# uzed-hmdi-test.net
KiCad netlist of a schematic drawn in EAGLE
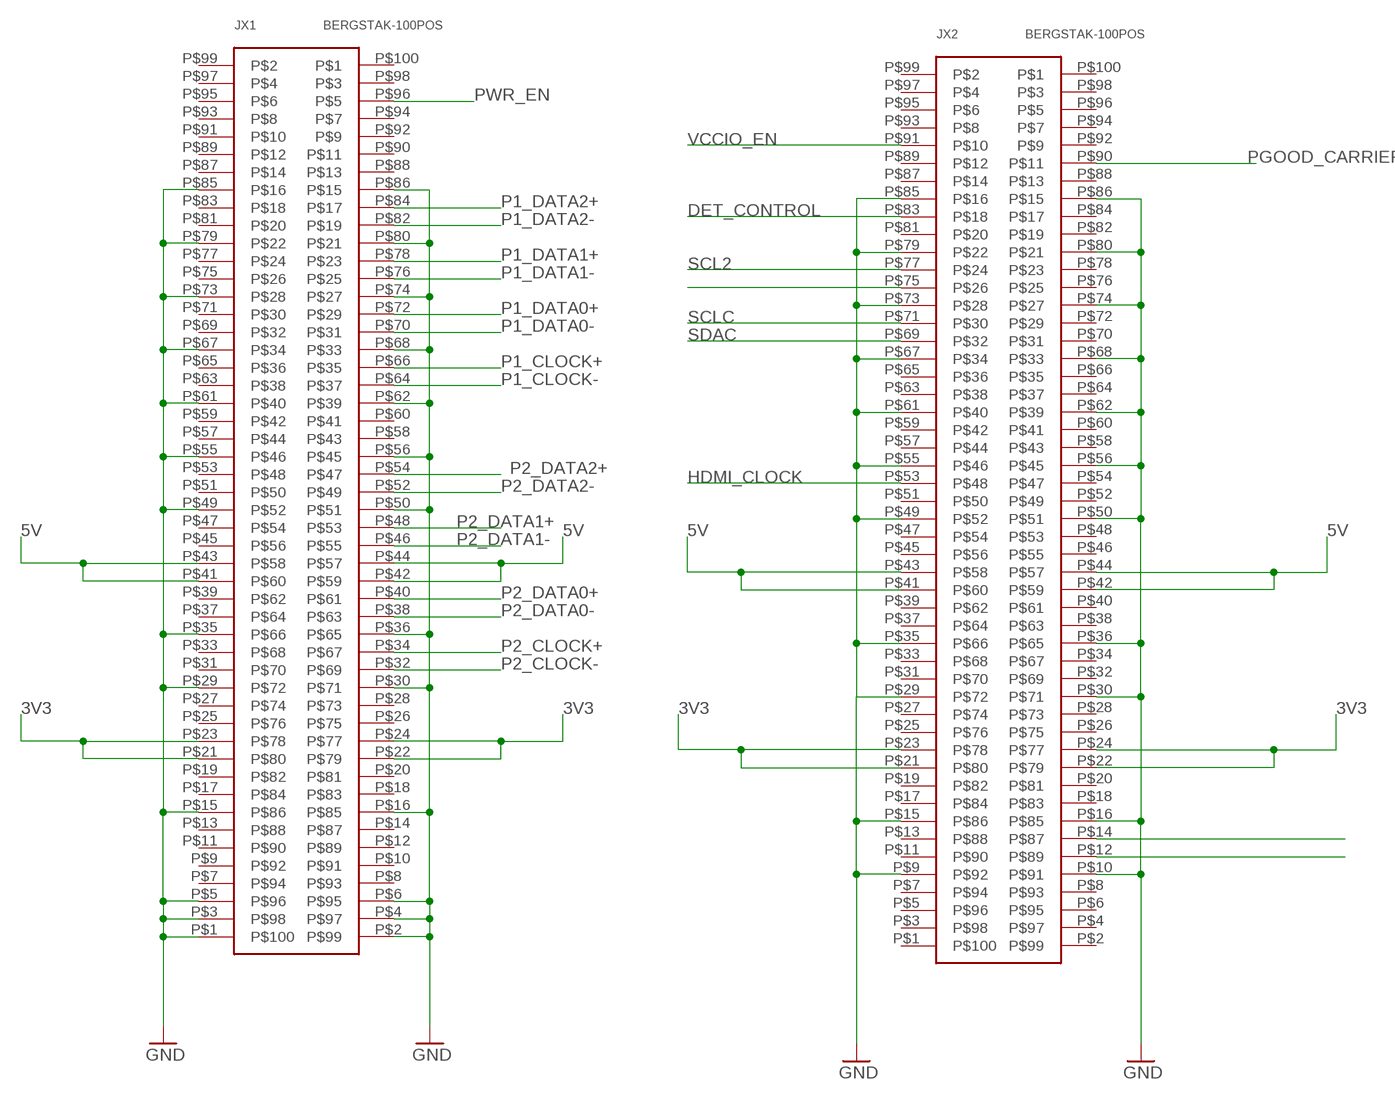
[diagram p0: schematic, sheet 1]
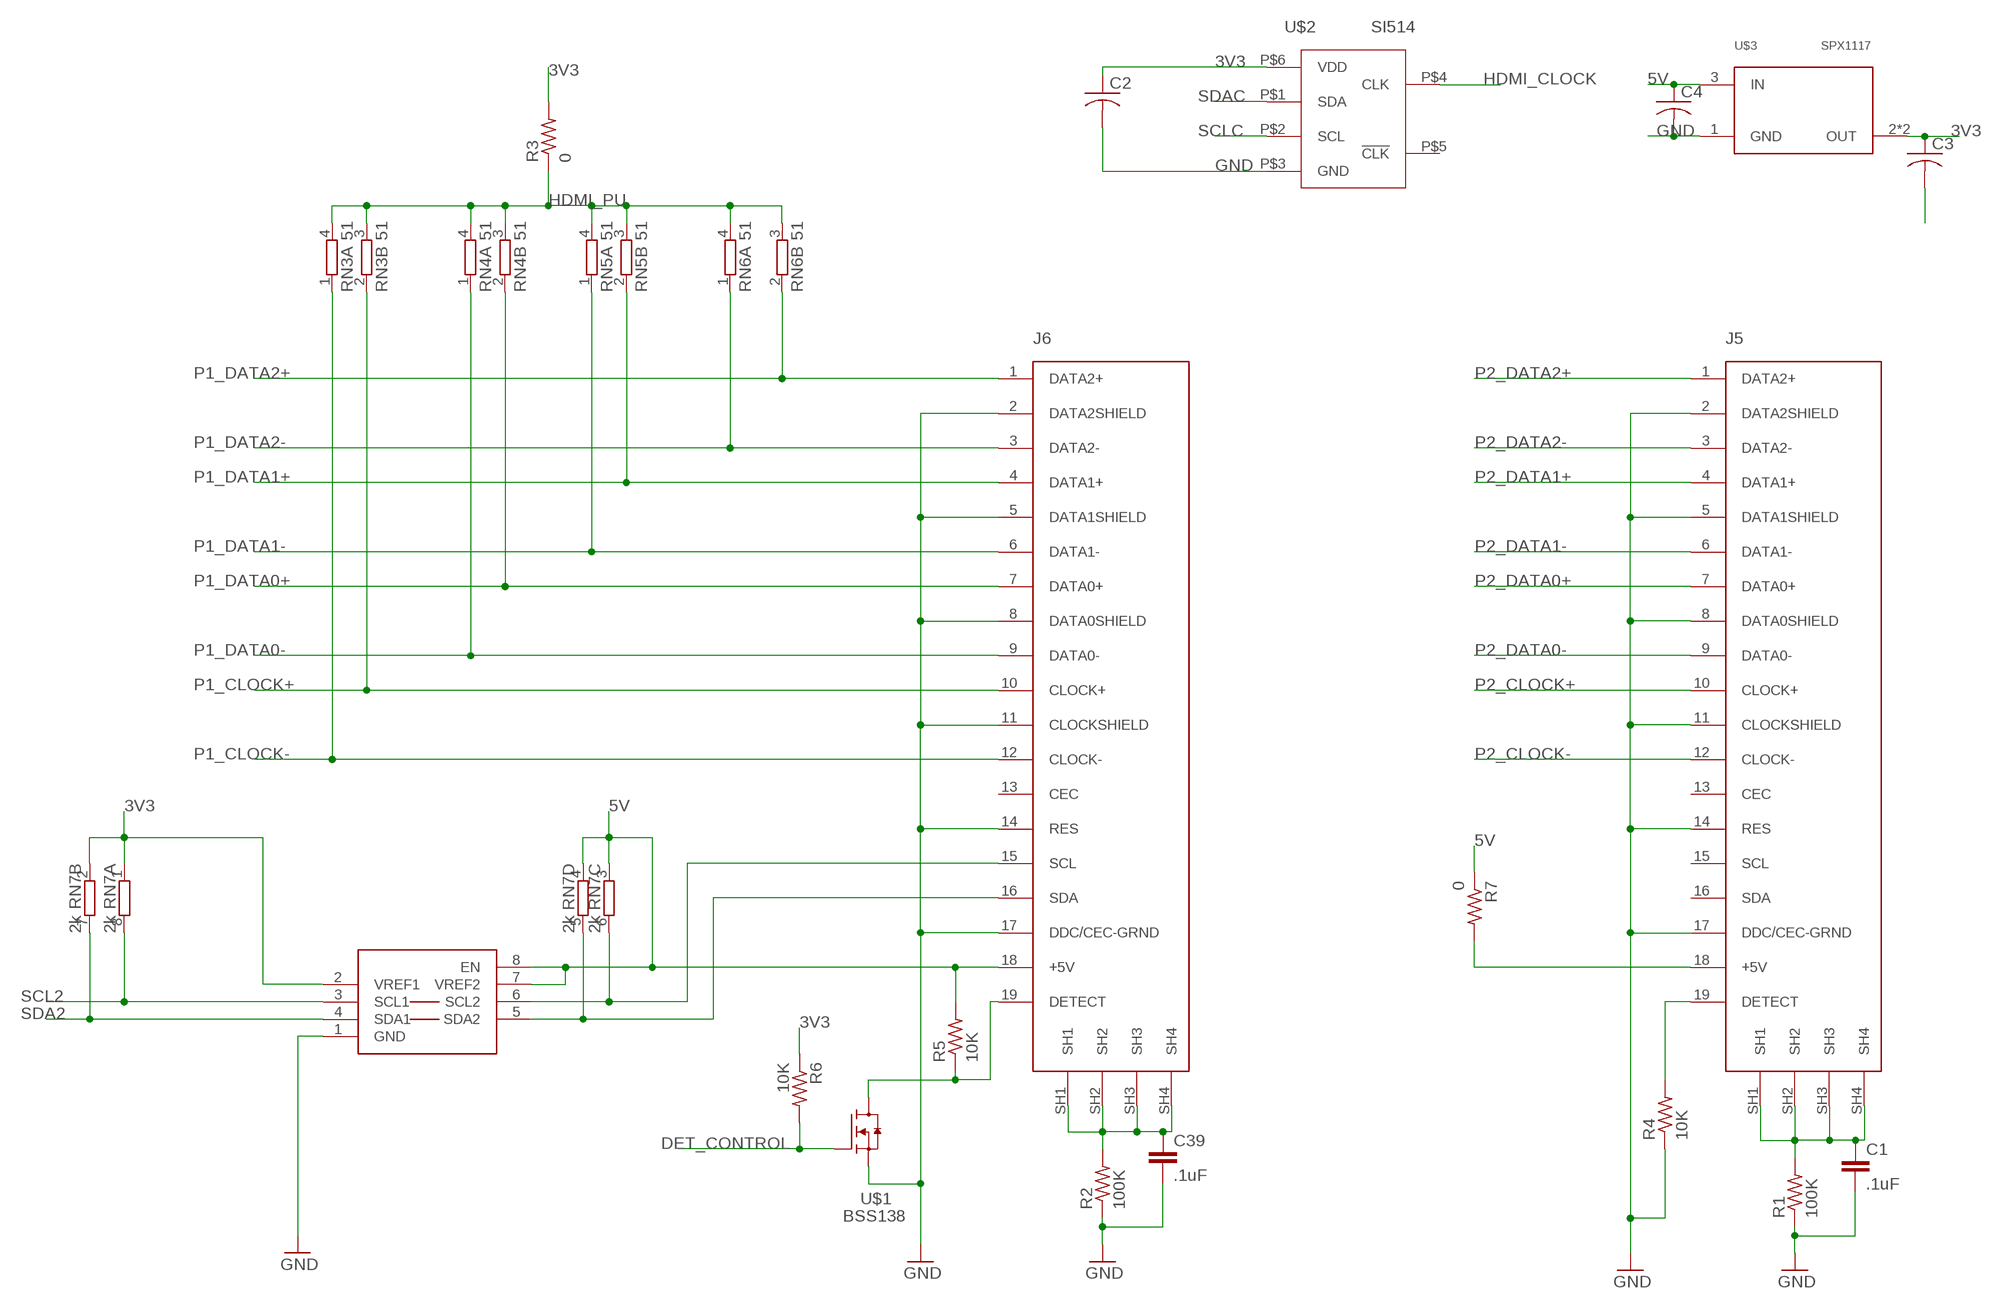
[diagram p1: schematic, sheet 2]

(export (version "E")
  (design (tool "Eeschema 10.0.6"))
  (components
    (comp (ref "JX1")
      (value "BERGSTAK-100POS")
      (footprint "eagle-import:BERG100POS")
      (libsource (lib "eagle-import") (part "BERGSTAK-100POS"))
    )
    (comp (ref "JX2")
      (value "BERGSTAK-100POS")
      (footprint "eagle-import:BERG100POS")
      (libsource (lib "eagle-import") (part "BERGSTAK-100POS"))
    )
    (comp (ref "C1")
      (value ".1uF")
      (footprint "eagle-import:C0603K")
      (libsource (lib "eagle-import") (part "C-EUC0603K"))
    )
    (comp (ref "C2")
      (value "C-USC0603")
      (footprint "eagle-import:C0603")
      (libsource (lib "eagle-import") (part "C-USC0603"))
    )
    (comp (ref "C3")
      (value "C-USC0603")
      (footprint "eagle-import:C0603")
      (libsource (lib "eagle-import") (part "C-USC0603"))
    )
    (comp (ref "C4")
      (value "C-USC0603")
      (footprint "eagle-import:C0603")
      (libsource (lib "eagle-import") (part "C-USC0603"))
    )
    (comp (ref "C39")
      (value ".1uF")
      (footprint "eagle-import:C0603K")
      (libsource (lib "eagle-import") (part "C-EUC0603K"))
    )
    (comp (ref "J5")
      (value "HDMI-TYPE-A-RECEPTICALFCI10029449")
      (footprint "eagle-import:FCI-HDMI-TYPE-A-RECEPT")
      (libsource (lib "eagle-import") (part "HDMI-TYPE-A-RECEPTICALFCI10029449"))
    )
    (comp (ref "J6")
      (value "HDMI-TYPE-A-RECEPTICALFCI10029449")
      (footprint "eagle-import:FCI-HDMI-TYPE-A-RECEPT")
      (libsource (lib "eagle-import") (part "HDMI-TYPE-A-RECEPTICALFCI10029449"))
    )
    (comp (ref "PCA9306")
      (value "PCA9306")
      (footprint "eagle-import:PSOP-8")
      (libsource (lib "eagle-import") (part "PCA9306"))
    )
    (comp (ref "R1")
      (value "100K")
      (footprint "eagle-import:R0603")
      (libsource (lib "eagle-import") (part "R-US_R0603"))
    )
    (comp (ref "R2")
      (value "100K")
      (footprint "eagle-import:R0603")
      (libsource (lib "eagle-import") (part "R-US_R0603"))
    )
    (comp (ref "R3")
      (value "0")
      (footprint "eagle-import:R0603")
      (libsource (lib "eagle-import") (part "rcl_334_R-US_R0603"))
    )
    (comp (ref "R4")
      (value "10K")
      (footprint "eagle-import:R0603")
      (libsource (lib "eagle-import") (part "R-US_R0603"))
    )
    (comp (ref "R5")
      (value "10K")
      (footprint "eagle-import:R0603")
      (libsource (lib "eagle-import") (part "R-US_R0603"))
    )
    (comp (ref "R6")
      (value "10K")
      (footprint "eagle-import:R0603")
      (libsource (lib "eagle-import") (part "R-US_R0603"))
    )
    (comp (ref "R7")
      (value "0")
      (footprint "eagle-import:R0603")
      (libsource (lib "eagle-import") (part "R-US_R0603"))
    )
    (comp (ref "RN3")
      (value "51")
      (footprint "eagle-import:EXB34V")
      (libsource (lib "eagle-import") (part "2R-NEXB34V"))
    )
    (comp (ref "RN4")
      (value "51")
      (footprint "eagle-import:EXB34V")
      (libsource (lib "eagle-import") (part "2R-NEXB34V"))
    )
    (comp (ref "RN5")
      (value "51")
      (footprint "eagle-import:EXB34V")
      (libsource (lib "eagle-import") (part "2R-NEXB34V"))
    )
    (comp (ref "RN6")
      (value "51")
      (footprint "eagle-import:EXB34V")
      (libsource (lib "eagle-import") (part "2R-NEXB34V"))
    )
    (comp (ref "RN7")
      (value "2k")
      (footprint "eagle-import:0603-ARV")
      (libsource (lib "eagle-import") (part "4R-N0603-ARV"))
    )
    (comp (ref "U$1")
      (value "BSS138")
      (footprint "eagle-import:SOT23")
      (libsource (lib "eagle-import") (part "BSS138"))
    )
    (comp (ref "U$2")
      (value "SI514")
      (footprint "eagle-import:XTAL-6PIN")
      (libsource (lib "eagle-import") (part "SI514"))
    )
    (comp (ref "U$3")
      (value "SPX1117")
      (footprint "eagle-import:SOT223")
      (libsource (lib "eagle-import") (part "SPX1117"))
    )
  )
  (nets
    (net (code "1") (name "3V3") (class "Default")
      (node (ref "C2") (pin "1") (pinfunction "1_1") (pintype "passive"))
      (node (ref "C3") (pin "1") (pinfunction "1_1") (pintype "passive"))
      (node (ref "JX1") (pin "P$21") (pinfunction "P$80_P$21") (pintype "bidirectional"))
      (node (ref "JX1") (pin "P$22") (pinfunction "P$79_P$22") (pintype "bidirectional"))
      (node (ref "JX1") (pin "P$23") (pinfunction "P$78_P$23") (pintype "bidirectional"))
      (node (ref "JX1") (pin "P$24") (pinfunction "P$77_P$24") (pintype "bidirectional"))
      (node (ref "JX2") (pin "P$21") (pinfunction "P$80_P$21") (pintype "bidirectional"))
      (node (ref "JX2") (pin "P$22") (pinfunction "P$79_P$22") (pintype "bidirectional"))
      (node (ref "JX2") (pin "P$23") (pinfunction "P$78_P$23") (pintype "bidirectional"))
      (node (ref "JX2") (pin "P$24") (pinfunction "P$77_P$24") (pintype "bidirectional"))
      (node (ref "PCA9306") (pin "2") (pinfunction "VREF1_2") (pintype "bidirectional"))
      (node (ref "R3") (pin "2") (pinfunction "2_2") (pintype "passive"))
      (node (ref "R6") (pin "1") (pinfunction "1_1") (pintype "passive"))
      (node (ref "RN7") (pin "1") (pinfunction "1_1") (pintype "passive"))
      (node (ref "RN7") (pin "2") (pinfunction "1_2") (pintype "passive"))
      (node (ref "U$2") (pin "P$6") (pinfunction "VDD_P$6") (pintype "bidirectional"))
      (node (ref "U$3") (pin "2") (pinfunction "OUT_2") (pintype "bidirectional"))
      (node (ref "U$3") (pin "4") (pinfunction "OUT_4") (pintype "bidirectional"))
    )
    (net (code "2") (name "5V") (class "Default")
      (node (ref "C4") (pin "1") (pinfunction "1_1") (pintype "passive"))
      (node (ref "J6") (pin "18") (pinfunction "+5V_18") (pintype "bidirectional"))
      (node (ref "JX1") (pin "P$41") (pinfunction "P$60_P$41") (pintype "bidirectional"))
      (node (ref "JX1") (pin "P$42") (pinfunction "P$59_P$42") (pintype "bidirectional"))
      (node (ref "JX1") (pin "P$43") (pinfunction "P$58_P$43") (pintype "bidirectional"))
      (node (ref "JX1") (pin "P$44") (pinfunction "P$57_P$44") (pintype "bidirectional"))
      (node (ref "JX2") (pin "P$41") (pinfunction "P$60_P$41") (pintype "bidirectional"))
      (node (ref "JX2") (pin "P$42") (pinfunction "P$59_P$42") (pintype "bidirectional"))
      (node (ref "JX2") (pin "P$43") (pinfunction "P$58_P$43") (pintype "bidirectional"))
      (node (ref "JX2") (pin "P$44") (pinfunction "P$57_P$44") (pintype "bidirectional"))
      (node (ref "PCA9306") (pin "7") (pinfunction "VREF2_7") (pintype "bidirectional"))
      (node (ref "PCA9306") (pin "8") (pinfunction "EN_8") (pintype "bidirectional"))
      (node (ref "R5") (pin "2") (pinfunction "2_2") (pintype "passive"))
      (node (ref "R7") (pin "1") (pinfunction "1_1") (pintype "passive"))
      (node (ref "RN7") (pin "3") (pinfunction "1_3") (pintype "passive"))
      (node (ref "RN7") (pin "4") (pinfunction "1_4") (pintype "passive"))
      (node (ref "U$3") (pin "3") (pinfunction "IN_3") (pintype "bidirectional"))
    )
    (net (code "3") (name "DET_CONTROL") (class "Default")
      (node (ref "JX2") (pin "P$83") (pinfunction "P$18_P$83") (pintype "bidirectional"))
      (node (ref "R6") (pin "2") (pinfunction "2_2") (pintype "passive"))
      (node (ref "U$1") (pin "1") (pinfunction "G_1") (pintype "passive"))
    )
    (net (code "4") (name "GND") (class "Default")
      (node (ref "C1") (pin "2") (pinfunction "2_2") (pintype "passive"))
      (node (ref "C2") (pin "2") (pinfunction "2_2") (pintype "passive"))
      (node (ref "C3") (pin "2") (pinfunction "2_2") (pintype "passive"))
      (node (ref "C39") (pin "2") (pinfunction "2_2") (pintype "passive"))
      (node (ref "C4") (pin "2") (pinfunction "2_2") (pintype "passive"))
      (node (ref "J5") (pin "11") (pinfunction "CLOCKSHIELD_11") (pintype "bidirectional"))
      (node (ref "J5") (pin "14") (pinfunction "RES_14") (pintype "bidirectional"))
      (node (ref "J5") (pin "17") (pinfunction "DDC/CEC-GRND_17") (pintype "bidirectional"))
      (node (ref "J5") (pin "2") (pinfunction "DATA2SHIELD_2") (pintype "bidirectional"))
      (node (ref "J5") (pin "5") (pinfunction "DATA1SHIELD_5") (pintype "bidirectional"))
      (node (ref "J5") (pin "8") (pinfunction "DATA0SHIELD_8") (pintype "bidirectional"))
      (node (ref "J6") (pin "11") (pinfunction "CLOCKSHIELD_11") (pintype "bidirectional"))
      (node (ref "J6") (pin "14") (pinfunction "RES_14") (pintype "bidirectional"))
      (node (ref "J6") (pin "17") (pinfunction "DDC/CEC-GRND_17") (pintype "bidirectional"))
      (node (ref "J6") (pin "2") (pinfunction "DATA2SHIELD_2") (pintype "bidirectional"))
      (node (ref "J6") (pin "5") (pinfunction "DATA1SHIELD_5") (pintype "bidirectional"))
      (node (ref "J6") (pin "8") (pinfunction "DATA0SHIELD_8") (pintype "bidirectional"))
      (node (ref "JX1") (pin "P$1") (pinfunction "P$100_P$1") (pintype "bidirectional"))
      (node (ref "JX1") (pin "P$15") (pinfunction "P$86_P$15") (pintype "bidirectional"))
      (node (ref "JX1") (pin "P$16") (pinfunction "P$85_P$16") (pintype "bidirectional"))
      (node (ref "JX1") (pin "P$2") (pinfunction "P$99_P$2") (pintype "bidirectional"))
      (node (ref "JX1") (pin "P$29") (pinfunction "P$72_P$29") (pintype "bidirectional"))
      (node (ref "JX1") (pin "P$3") (pinfunction "P$98_P$3") (pintype "bidirectional"))
      (node (ref "JX1") (pin "P$30") (pinfunction "P$71_P$30") (pintype "bidirectional"))
      (node (ref "JX1") (pin "P$35") (pinfunction "P$66_P$35") (pintype "bidirectional"))
      (node (ref "JX1") (pin "P$36") (pinfunction "P$65_P$36") (pintype "bidirectional"))
      (node (ref "JX1") (pin "P$4") (pinfunction "P$97_P$4") (pintype "bidirectional"))
      (node (ref "JX1") (pin "P$49") (pinfunction "P$52_P$49") (pintype "bidirectional"))
      (node (ref "JX1") (pin "P$5") (pinfunction "P$96_P$5") (pintype "bidirectional"))
      (node (ref "JX1") (pin "P$50") (pinfunction "P$51_P$50") (pintype "bidirectional"))
      (node (ref "JX1") (pin "P$55") (pinfunction "P$46_P$55") (pintype "bidirectional"))
      (node (ref "JX1") (pin "P$56") (pinfunction "P$45_P$56") (pintype "bidirectional"))
      (node (ref "JX1") (pin "P$6") (pinfunction "P$95_P$6") (pintype "bidirectional"))
      (node (ref "JX1") (pin "P$61") (pinfunction "P$40_P$61") (pintype "bidirectional"))
      (node (ref "JX1") (pin "P$62") (pinfunction "P$39_P$62") (pintype "bidirectional"))
      (node (ref "JX1") (pin "P$67") (pinfunction "P$34_P$67") (pintype "bidirectional"))
      (node (ref "JX1") (pin "P$68") (pinfunction "P$33_P$68") (pintype "bidirectional"))
      (node (ref "JX1") (pin "P$73") (pinfunction "P$28_P$73") (pintype "bidirectional"))
      (node (ref "JX1") (pin "P$74") (pinfunction "P$27_P$74") (pintype "bidirectional"))
      (node (ref "JX1") (pin "P$79") (pinfunction "P$22_P$79") (pintype "bidirectional"))
      (node (ref "JX1") (pin "P$80") (pinfunction "P$21_P$80") (pintype "bidirectional"))
      (node (ref "JX1") (pin "P$85") (pinfunction "P$16_P$85") (pintype "bidirectional"))
      (node (ref "JX1") (pin "P$86") (pinfunction "P$15_P$86") (pintype "bidirectional"))
      (node (ref "JX2") (pin "P$10") (pinfunction "P$91_P$10") (pintype "bidirectional"))
      (node (ref "JX2") (pin "P$15") (pinfunction "P$86_P$15") (pintype "bidirectional"))
      (node (ref "JX2") (pin "P$16") (pinfunction "P$85_P$16") (pintype "bidirectional"))
      (node (ref "JX2") (pin "P$29") (pinfunction "P$72_P$29") (pintype "bidirectional"))
      (node (ref "JX2") (pin "P$30") (pinfunction "P$71_P$30") (pintype "bidirectional"))
      (node (ref "JX2") (pin "P$35") (pinfunction "P$66_P$35") (pintype "bidirectional"))
      (node (ref "JX2") (pin "P$36") (pinfunction "P$65_P$36") (pintype "bidirectional"))
      (node (ref "JX2") (pin "P$49") (pinfunction "P$52_P$49") (pintype "bidirectional"))
      (node (ref "JX2") (pin "P$50") (pinfunction "P$51_P$50") (pintype "bidirectional"))
      (node (ref "JX2") (pin "P$55") (pinfunction "P$46_P$55") (pintype "bidirectional"))
      (node (ref "JX2") (pin "P$56") (pinfunction "P$45_P$56") (pintype "bidirectional"))
      (node (ref "JX2") (pin "P$61") (pinfunction "P$40_P$61") (pintype "bidirectional"))
      (node (ref "JX2") (pin "P$62") (pinfunction "P$39_P$62") (pintype "bidirectional"))
      (node (ref "JX2") (pin "P$67") (pinfunction "P$34_P$67") (pintype "bidirectional"))
      (node (ref "JX2") (pin "P$68") (pinfunction "P$33_P$68") (pintype "bidirectional"))
      (node (ref "JX2") (pin "P$73") (pinfunction "P$28_P$73") (pintype "bidirectional"))
      (node (ref "JX2") (pin "P$74") (pinfunction "P$27_P$74") (pintype "bidirectional"))
      (node (ref "JX2") (pin "P$79") (pinfunction "P$22_P$79") (pintype "bidirectional"))
      (node (ref "JX2") (pin "P$80") (pinfunction "P$21_P$80") (pintype "bidirectional"))
      (node (ref "JX2") (pin "P$85") (pinfunction "P$16_P$85") (pintype "bidirectional"))
      (node (ref "JX2") (pin "P$86") (pinfunction "P$15_P$86") (pintype "bidirectional"))
      (node (ref "JX2") (pin "P$9") (pinfunction "P$92_P$9") (pintype "bidirectional"))
      (node (ref "PCA9306") (pin "1") (pinfunction "GND_1") (pintype "bidirectional"))
      (node (ref "R1") (pin "1") (pinfunction "1_1") (pintype "passive"))
      (node (ref "R2") (pin "1") (pinfunction "1_1") (pintype "passive"))
      (node (ref "R4") (pin "1") (pinfunction "1_1") (pintype "passive"))
      (node (ref "U$1") (pin "2") (pinfunction "S_2") (pintype "passive"))
      (node (ref "U$2") (pin "P$3") (pinfunction "GND_P$3") (pintype "bidirectional"))
      (node (ref "U$3") (pin "1") (pinfunction "GND_1") (pintype "bidirectional"))
    )
    (net (code "5") (name "HDMI_CLOCK") (class "Default")
      (node (ref "JX2") (pin "P$53") (pinfunction "P$48_P$53") (pintype "bidirectional"))
      (node (ref "U$2") (pin "P$4") (pinfunction "CLK_P$4") (pintype "bidirectional"))
    )
    (net (code "6") (name "HDMI_PU") (class "Default")
      (node (ref "R3") (pin "1") (pinfunction "1_1") (pintype "passive"))
      (node (ref "RN3") (pin "3") (pinfunction "2_3") (pintype "passive"))
      (node (ref "RN3") (pin "4") (pinfunction "2_4") (pintype "passive"))
      (node (ref "RN4") (pin "3") (pinfunction "2_3") (pintype "passive"))
      (node (ref "RN4") (pin "4") (pinfunction "2_4") (pintype "passive"))
      (node (ref "RN5") (pin "3") (pinfunction "2_3") (pintype "passive"))
      (node (ref "RN5") (pin "4") (pinfunction "2_4") (pintype "passive"))
      (node (ref "RN6") (pin "3") (pinfunction "2_3") (pintype "passive"))
      (node (ref "RN6") (pin "4") (pinfunction "2_4") (pintype "passive"))
    )
    (net (code "7") (name "Net-(C1-Pad1)") (class "Default")
      (node (ref "C1") (pin "1") (pinfunction "1_1") (pintype "passive"))
      (node (ref "J5") (pin "SH1") (pinfunction "SH1_SH1") (pintype "bidirectional"))
      (node (ref "J5") (pin "SH2") (pinfunction "SH2_SH2") (pintype "bidirectional"))
      (node (ref "J5") (pin "SH3") (pinfunction "SH3_SH3") (pintype "bidirectional"))
      (node (ref "J5") (pin "SH4") (pinfunction "SH4_SH4") (pintype "bidirectional"))
      (node (ref "R1") (pin "2") (pinfunction "2_2") (pintype "passive"))
    )
    (net (code "8") (name "Net-(C39-Pad1)") (class "Default")
      (node (ref "C39") (pin "1") (pinfunction "1_1") (pintype "passive"))
      (node (ref "J6") (pin "SH1") (pinfunction "SH1_SH1") (pintype "bidirectional"))
      (node (ref "J6") (pin "SH2") (pinfunction "SH2_SH2") (pintype "bidirectional"))
      (node (ref "J6") (pin "SH3") (pinfunction "SH3_SH3") (pintype "bidirectional"))
      (node (ref "J6") (pin "SH4") (pinfunction "SH4_SH4") (pintype "bidirectional"))
      (node (ref "R2") (pin "2") (pinfunction "2_2") (pintype "passive"))
    )
    (net (code "9") (name "Net-(J5-+5V)") (class "Default")
      (node (ref "J5") (pin "18") (pinfunction "+5V_18") (pintype "bidirectional"))
      (node (ref "R7") (pin "2") (pinfunction "2_2") (pintype "passive"))
    )
    (net (code "10") (name "Net-(J5-DETECT)") (class "Default")
      (node (ref "J5") (pin "19") (pinfunction "DETECT_19") (pintype "bidirectional"))
      (node (ref "R4") (pin "2") (pinfunction "2_2") (pintype "passive"))
    )
    (net (code "11") (name "Net-(J6-DETECT)") (class "Default")
      (node (ref "J6") (pin "19") (pinfunction "DETECT_19") (pintype "bidirectional"))
      (node (ref "R5") (pin "1") (pinfunction "1_1") (pintype "passive"))
      (node (ref "U$1") (pin "3") (pinfunction "D_3") (pintype "passive"))
    )
    (net (code "12") (name "Net-(J6-SCL)") (class "Default")
      (node (ref "J6") (pin "15") (pinfunction "SCL_15") (pintype "bidirectional"))
      (node (ref "PCA9306") (pin "6") (pinfunction "SCL2_6") (pintype "bidirectional"))
      (node (ref "RN7") (pin "6") (pinfunction "2_6") (pintype "passive"))
    )
    (net (code "13") (name "Net-(J6-SDA)") (class "Default")
      (node (ref "J6") (pin "16") (pinfunction "SDA_16") (pintype "bidirectional"))
      (node (ref "PCA9306") (pin "5") (pinfunction "SDA2_5") (pintype "bidirectional"))
      (node (ref "RN7") (pin "5") (pinfunction "2_5") (pintype "passive"))
    )
    (net (code "14") (name "P1_CLOCK+") (class "Default")
      (node (ref "J6") (pin "10") (pinfunction "CLOCK+_10") (pintype "bidirectional"))
      (node (ref "JX1") (pin "P$66") (pinfunction "P$35_P$66") (pintype "bidirectional"))
      (node (ref "RN3") (pin "2") (pinfunction "1_2") (pintype "passive"))
    )
    (net (code "15") (name "P1_CLOCK-") (class "Default")
      (node (ref "J6") (pin "12") (pinfunction "CLOCK-_12") (pintype "bidirectional"))
      (node (ref "JX1") (pin "P$64") (pinfunction "P$37_P$64") (pintype "bidirectional"))
      (node (ref "RN3") (pin "1") (pinfunction "1_1") (pintype "passive"))
    )
    (net (code "16") (name "P1_DATA0+") (class "Default")
      (node (ref "J6") (pin "7") (pinfunction "DATA0+_7") (pintype "bidirectional"))
      (node (ref "JX1") (pin "P$72") (pinfunction "P$29_P$72") (pintype "bidirectional"))
      (node (ref "RN4") (pin "2") (pinfunction "1_2") (pintype "passive"))
    )
    (net (code "17") (name "P1_DATA0-") (class "Default")
      (node (ref "J6") (pin "9") (pinfunction "DATA0-_9") (pintype "bidirectional"))
      (node (ref "JX1") (pin "P$70") (pinfunction "P$31_P$70") (pintype "bidirectional"))
      (node (ref "RN4") (pin "1") (pinfunction "1_1") (pintype "passive"))
    )
    (net (code "18") (name "P1_DATA1+") (class "Default")
      (node (ref "J6") (pin "4") (pinfunction "DATA1+_4") (pintype "bidirectional"))
      (node (ref "JX1") (pin "P$78") (pinfunction "P$23_P$78") (pintype "bidirectional"))
      (node (ref "RN5") (pin "2") (pinfunction "1_2") (pintype "passive"))
    )
    (net (code "19") (name "P1_DATA1-") (class "Default")
      (node (ref "J6") (pin "6") (pinfunction "DATA1-_6") (pintype "bidirectional"))
      (node (ref "JX1") (pin "P$76") (pinfunction "P$25_P$76") (pintype "bidirectional"))
      (node (ref "RN5") (pin "1") (pinfunction "1_1") (pintype "passive"))
    )
    (net (code "20") (name "P1_DATA2+") (class "Default")
      (node (ref "J6") (pin "1") (pinfunction "DATA2+_1") (pintype "bidirectional"))
      (node (ref "JX1") (pin "P$84") (pinfunction "P$17_P$84") (pintype "bidirectional"))
      (node (ref "RN6") (pin "2") (pinfunction "1_2") (pintype "passive"))
    )
    (net (code "21") (name "P1_DATA2-") (class "Default")
      (node (ref "J6") (pin "3") (pinfunction "DATA2-_3") (pintype "bidirectional"))
      (node (ref "JX1") (pin "P$82") (pinfunction "P$19_P$82") (pintype "bidirectional"))
      (node (ref "RN6") (pin "1") (pinfunction "1_1") (pintype "passive"))
    )
    (net (code "22") (name "P2_CLOCK+") (class "Default")
      (node (ref "J5") (pin "10") (pinfunction "CLOCK+_10") (pintype "bidirectional"))
      (node (ref "JX1") (pin "P$34") (pinfunction "P$67_P$34") (pintype "bidirectional"))
    )
    (net (code "23") (name "P2_CLOCK-") (class "Default")
      (node (ref "J5") (pin "12") (pinfunction "CLOCK-_12") (pintype "bidirectional"))
      (node (ref "JX1") (pin "P$32") (pinfunction "P$69_P$32") (pintype "bidirectional"))
    )
    (net (code "24") (name "P2_DATA0+") (class "Default")
      (node (ref "J5") (pin "7") (pinfunction "DATA0+_7") (pintype "bidirectional"))
      (node (ref "JX1") (pin "P$40") (pinfunction "P$61_P$40") (pintype "bidirectional"))
    )
    (net (code "25") (name "P2_DATA0-") (class "Default")
      (node (ref "J5") (pin "9") (pinfunction "DATA0-_9") (pintype "bidirectional"))
      (node (ref "JX1") (pin "P$38") (pinfunction "P$63_P$38") (pintype "bidirectional"))
    )
    (net (code "26") (name "P2_DATA1+") (class "Default")
      (node (ref "J5") (pin "4") (pinfunction "DATA1+_4") (pintype "bidirectional"))
      (node (ref "JX1") (pin "P$48") (pinfunction "P$53_P$48") (pintype "bidirectional"))
    )
    (net (code "27") (name "P2_DATA1-") (class "Default")
      (node (ref "J5") (pin "6") (pinfunction "DATA1-_6") (pintype "bidirectional"))
      (node (ref "JX1") (pin "P$46") (pinfunction "P$55_P$46") (pintype "bidirectional"))
    )
    (net (code "28") (name "P2_DATA2+") (class "Default")
      (node (ref "J5") (pin "1") (pinfunction "DATA2+_1") (pintype "bidirectional"))
      (node (ref "JX1") (pin "P$54") (pinfunction "P$47_P$54") (pintype "bidirectional"))
    )
    (net (code "29") (name "P2_DATA2-") (class "Default")
      (node (ref "J5") (pin "3") (pinfunction "DATA2-_3") (pintype "bidirectional"))
      (node (ref "JX1") (pin "P$52") (pinfunction "P$49_P$52") (pintype "bidirectional"))
    )
    (net (code "30") (name "PGOOD_CARRIER") (class "Default")
      (node (ref "JX2") (pin "P$90") (pinfunction "P$11_P$90") (pintype "bidirectional"))
    )
    (net (code "31") (name "PWR_EN") (class "Default")
      (node (ref "JX1") (pin "P$96") (pinfunction "P$5_P$96") (pintype "bidirectional"))
    )
    (net (code "32") (name "SCL2") (class "Default")
      (node (ref "JX2") (pin "P$77") (pinfunction "P$24_P$77") (pintype "bidirectional"))
      (node (ref "PCA9306") (pin "3") (pinfunction "SCL1_3") (pintype "bidirectional"))
      (node (ref "RN7") (pin "8") (pinfunction "2_8") (pintype "passive"))
    )
    (net (code "33") (name "SCLC") (class "Default")
      (node (ref "JX2") (pin "P$71") (pinfunction "P$30_P$71") (pintype "bidirectional"))
      (node (ref "U$2") (pin "P$2") (pinfunction "SCL_P$2") (pintype "bidirectional"))
    )
    (net (code "34") (name "SDA2") (class "Default")
      (node (ref "JX2") (pin "P$75") (pinfunction "P$26_P$75") (pintype "bidirectional"))
      (node (ref "PCA9306") (pin "4") (pinfunction "SDA1_4") (pintype "bidirectional"))
      (node (ref "RN7") (pin "7") (pinfunction "2_7") (pintype "passive"))
    )
    (net (code "35") (name "SDAC") (class "Default")
      (node (ref "JX2") (pin "P$69") (pinfunction "P$32_P$69") (pintype "bidirectional"))
      (node (ref "U$2") (pin "P$1") (pinfunction "SDA_P$1") (pintype "bidirectional"))
    )
    (net (code "36") (name "VCCIO_EN") (class "Default")
      (node (ref "JX2") (pin "P$91") (pinfunction "P$10_P$91") (pintype "bidirectional"))
    )
    (net (code "37") (name "unconnected-(J5-CEC-Pad13)") (class "Default")
      (node (ref "J5") (pin "13") (pinfunction "CEC_13") (pintype "bidirectional"))
    )
    (net (code "38") (name "unconnected-(J5-SCL-Pad15)") (class "Default")
      (node (ref "J5") (pin "15") (pinfunction "SCL_15") (pintype "bidirectional"))
    )
    (net (code "39") (name "unconnected-(J5-SDA-Pad16)") (class "Default")
      (node (ref "J5") (pin "16") (pinfunction "SDA_16") (pintype "bidirectional"))
    )
    (net (code "40") (name "unconnected-(J6-CEC-Pad13)") (class "Default")
      (node (ref "J6") (pin "13") (pinfunction "CEC_13") (pintype "bidirectional"))
    )
    (net (code "41") (name "unconnected-(JX1-P$1-PadP$100)") (class "Default")
      (node (ref "JX1") (pin "P$100") (pinfunction "P$1_P$100") (pintype "bidirectional"))
    )
    (net (code "42") (name "unconnected-(JX1-P$2-PadP$99)") (class "Default")
      (node (ref "JX1") (pin "P$99") (pinfunction "P$2_P$99") (pintype "bidirectional"))
    )
    (net (code "43") (name "unconnected-(JX1-P$3-PadP$98)") (class "Default")
      (node (ref "JX1") (pin "P$98") (pinfunction "P$3_P$98") (pintype "bidirectional"))
    )
    (net (code "44") (name "unconnected-(JX1-P$4-PadP$97)") (class "Default")
      (node (ref "JX1") (pin "P$97") (pinfunction "P$4_P$97") (pintype "bidirectional"))
    )
    (net (code "45") (name "unconnected-(JX1-P$6-PadP$95)") (class "Default")
      (node (ref "JX1") (pin "P$95") (pinfunction "P$6_P$95") (pintype "bidirectional"))
    )
    (net (code "46") (name "unconnected-(JX1-P$7-PadP$94)") (class "Default")
      (node (ref "JX1") (pin "P$94") (pinfunction "P$7_P$94") (pintype "bidirectional"))
    )
    (net (code "47") (name "unconnected-(JX1-P$8-PadP$93)") (class "Default")
      (node (ref "JX1") (pin "P$93") (pinfunction "P$8_P$93") (pintype "bidirectional"))
    )
    (net (code "48") (name "unconnected-(JX1-P$9-PadP$92)") (class "Default")
      (node (ref "JX1") (pin "P$92") (pinfunction "P$9_P$92") (pintype "bidirectional"))
    )
    (net (code "49") (name "unconnected-(JX1-P$10-PadP$91)") (class "Default")
      (node (ref "JX1") (pin "P$91") (pinfunction "P$10_P$91") (pintype "bidirectional"))
    )
    (net (code "50") (name "unconnected-(JX1-P$11-PadP$90)") (class "Default")
      (node (ref "JX1") (pin "P$90") (pinfunction "P$11_P$90") (pintype "bidirectional"))
    )
    (net (code "51") (name "unconnected-(JX1-P$12-PadP$89)") (class "Default")
      (node (ref "JX1") (pin "P$89") (pinfunction "P$12_P$89") (pintype "bidirectional"))
    )
    (net (code "52") (name "unconnected-(JX1-P$13-PadP$88)") (class "Default")
      (node (ref "JX1") (pin "P$88") (pinfunction "P$13_P$88") (pintype "bidirectional"))
    )
    (net (code "53") (name "unconnected-(JX1-P$14-PadP$87)") (class "Default")
      (node (ref "JX1") (pin "P$87") (pinfunction "P$14_P$87") (pintype "bidirectional"))
    )
    (net (code "54") (name "unconnected-(JX1-P$18-PadP$83)") (class "Default")
      (node (ref "JX1") (pin "P$83") (pinfunction "P$18_P$83") (pintype "bidirectional"))
    )
    (net (code "55") (name "unconnected-(JX1-P$20-PadP$81)") (class "Default")
      (node (ref "JX1") (pin "P$81") (pinfunction "P$20_P$81") (pintype "bidirectional"))
    )
    (net (code "56") (name "unconnected-(JX1-P$24-PadP$77)") (class "Default")
      (node (ref "JX1") (pin "P$77") (pinfunction "P$24_P$77") (pintype "bidirectional"))
    )
    (net (code "57") (name "unconnected-(JX1-P$26-PadP$75)") (class "Default")
      (node (ref "JX1") (pin "P$75") (pinfunction "P$26_P$75") (pintype "bidirectional"))
    )
    (net (code "58") (name "unconnected-(JX1-P$30-PadP$71)") (class "Default")
      (node (ref "JX1") (pin "P$71") (pinfunction "P$30_P$71") (pintype "bidirectional"))
    )
    (net (code "59") (name "unconnected-(JX1-P$32-PadP$69)") (class "Default")
      (node (ref "JX1") (pin "P$69") (pinfunction "P$32_P$69") (pintype "bidirectional"))
    )
    (net (code "60") (name "unconnected-(JX1-P$36-PadP$65)") (class "Default")
      (node (ref "JX1") (pin "P$65") (pinfunction "P$36_P$65") (pintype "bidirectional"))
    )
    (net (code "61") (name "unconnected-(JX1-P$38-PadP$63)") (class "Default")
      (node (ref "JX1") (pin "P$63") (pinfunction "P$38_P$63") (pintype "bidirectional"))
    )
    (net (code "62") (name "unconnected-(JX1-P$41-PadP$60)") (class "Default")
      (node (ref "JX1") (pin "P$60") (pinfunction "P$41_P$60") (pintype "bidirectional"))
    )
    (net (code "63") (name "unconnected-(JX1-P$42-PadP$59)") (class "Default")
      (node (ref "JX1") (pin "P$59") (pinfunction "P$42_P$59") (pintype "bidirectional"))
    )
    (net (code "64") (name "unconnected-(JX1-P$43-PadP$58)") (class "Default")
      (node (ref "JX1") (pin "P$58") (pinfunction "P$43_P$58") (pintype "bidirectional"))
    )
    (net (code "65") (name "unconnected-(JX1-P$44-PadP$57)") (class "Default")
      (node (ref "JX1") (pin "P$57") (pinfunction "P$44_P$57") (pintype "bidirectional"))
    )
    (net (code "66") (name "unconnected-(JX1-P$48-PadP$53)") (class "Default")
      (node (ref "JX1") (pin "P$53") (pinfunction "P$48_P$53") (pintype "bidirectional"))
    )
    (net (code "67") (name "unconnected-(JX1-P$50-PadP$51)") (class "Default")
      (node (ref "JX1") (pin "P$51") (pinfunction "P$50_P$51") (pintype "bidirectional"))
    )
    (net (code "68") (name "unconnected-(JX1-P$54-PadP$47)") (class "Default")
      (node (ref "JX1") (pin "P$47") (pinfunction "P$54_P$47") (pintype "bidirectional"))
    )
    (net (code "69") (name "unconnected-(JX1-P$56-PadP$45)") (class "Default")
      (node (ref "JX1") (pin "P$45") (pinfunction "P$56_P$45") (pintype "bidirectional"))
    )
    (net (code "70") (name "unconnected-(JX1-P$62-PadP$39)") (class "Default")
      (node (ref "JX1") (pin "P$39") (pinfunction "P$62_P$39") (pintype "bidirectional"))
    )
    (net (code "71") (name "unconnected-(JX1-P$64-PadP$37)") (class "Default")
      (node (ref "JX1") (pin "P$37") (pinfunction "P$64_P$37") (pintype "bidirectional"))
    )
    (net (code "72") (name "unconnected-(JX1-P$68-PadP$33)") (class "Default")
      (node (ref "JX1") (pin "P$33") (pinfunction "P$68_P$33") (pintype "bidirectional"))
    )
    (net (code "73") (name "unconnected-(JX1-P$70-PadP$31)") (class "Default")
      (node (ref "JX1") (pin "P$31") (pinfunction "P$70_P$31") (pintype "bidirectional"))
    )
    (net (code "74") (name "unconnected-(JX1-P$73-PadP$28)") (class "Default")
      (node (ref "JX1") (pin "P$28") (pinfunction "P$73_P$28") (pintype "bidirectional"))
    )
    (net (code "75") (name "unconnected-(JX1-P$74-PadP$27)") (class "Default")
      (node (ref "JX1") (pin "P$27") (pinfunction "P$74_P$27") (pintype "bidirectional"))
    )
    (net (code "76") (name "unconnected-(JX1-P$75-PadP$26)") (class "Default")
      (node (ref "JX1") (pin "P$26") (pinfunction "P$75_P$26") (pintype "bidirectional"))
    )
    (net (code "77") (name "unconnected-(JX1-P$76-PadP$25)") (class "Default")
      (node (ref "JX1") (pin "P$25") (pinfunction "P$76_P$25") (pintype "bidirectional"))
    )
    (net (code "78") (name "unconnected-(JX1-P$81-PadP$20)") (class "Default")
      (node (ref "JX1") (pin "P$20") (pinfunction "P$81_P$20") (pintype "bidirectional"))
    )
    (net (code "79") (name "unconnected-(JX1-P$82-PadP$19)") (class "Default")
      (node (ref "JX1") (pin "P$19") (pinfunction "P$82_P$19") (pintype "bidirectional"))
    )
    (net (code "80") (name "unconnected-(JX1-P$83-PadP$18)") (class "Default")
      (node (ref "JX1") (pin "P$18") (pinfunction "P$83_P$18") (pintype "bidirectional"))
    )
    (net (code "81") (name "unconnected-(JX1-P$84-PadP$17)") (class "Default")
      (node (ref "JX1") (pin "P$17") (pinfunction "P$84_P$17") (pintype "bidirectional"))
    )
    (net (code "82") (name "unconnected-(JX1-P$87-PadP$14)") (class "Default")
      (node (ref "JX1") (pin "P$14") (pinfunction "P$87_P$14") (pintype "bidirectional"))
    )
    (net (code "83") (name "unconnected-(JX1-P$88-PadP$13)") (class "Default")
      (node (ref "JX1") (pin "P$13") (pinfunction "P$88_P$13") (pintype "bidirectional"))
    )
    (net (code "84") (name "unconnected-(JX1-P$89-PadP$12)") (class "Default")
      (node (ref "JX1") (pin "P$12") (pinfunction "P$89_P$12") (pintype "bidirectional"))
    )
    (net (code "85") (name "unconnected-(JX1-P$90-PadP$11)") (class "Default")
      (node (ref "JX1") (pin "P$11") (pinfunction "P$90_P$11") (pintype "bidirectional"))
    )
    (net (code "86") (name "unconnected-(JX1-P$91-PadP$10)") (class "Default")
      (node (ref "JX1") (pin "P$10") (pinfunction "P$91_P$10") (pintype "bidirectional"))
    )
    (net (code "87") (name "unconnected-(JX1-P$92-PadP$9)") (class "Default")
      (node (ref "JX1") (pin "P$9") (pinfunction "P$92_P$9") (pintype "bidirectional"))
    )
    (net (code "88") (name "unconnected-(JX1-P$93-PadP$8)") (class "Default")
      (node (ref "JX1") (pin "P$8") (pinfunction "P$93_P$8") (pintype "bidirectional"))
    )
    (net (code "89") (name "unconnected-(JX1-P$94-PadP$7)") (class "Default")
      (node (ref "JX1") (pin "P$7") (pinfunction "P$94_P$7") (pintype "bidirectional"))
    )
    (net (code "90") (name "unconnected-(JX2-P$1-PadP$100)") (class "Default")
      (node (ref "JX2") (pin "P$100") (pinfunction "P$1_P$100") (pintype "bidirectional"))
    )
    (net (code "91") (name "unconnected-(JX2-P$2-PadP$99)") (class "Default")
      (node (ref "JX2") (pin "P$99") (pinfunction "P$2_P$99") (pintype "bidirectional"))
    )
    (net (code "92") (name "unconnected-(JX2-P$3-PadP$98)") (class "Default")
      (node (ref "JX2") (pin "P$98") (pinfunction "P$3_P$98") (pintype "bidirectional"))
    )
    (net (code "93") (name "unconnected-(JX2-P$4-PadP$97)") (class "Default")
      (node (ref "JX2") (pin "P$97") (pinfunction "P$4_P$97") (pintype "bidirectional"))
    )
    (net (code "94") (name "unconnected-(JX2-P$5-PadP$96)") (class "Default")
      (node (ref "JX2") (pin "P$96") (pinfunction "P$5_P$96") (pintype "bidirectional"))
    )
    (net (code "95") (name "unconnected-(JX2-P$6-PadP$95)") (class "Default")
      (node (ref "JX2") (pin "P$95") (pinfunction "P$6_P$95") (pintype "bidirectional"))
    )
    (net (code "96") (name "unconnected-(JX2-P$7-PadP$94)") (class "Default")
      (node (ref "JX2") (pin "P$94") (pinfunction "P$7_P$94") (pintype "bidirectional"))
    )
    (net (code "97") (name "unconnected-(JX2-P$8-PadP$93)") (class "Default")
      (node (ref "JX2") (pin "P$93") (pinfunction "P$8_P$93") (pintype "bidirectional"))
    )
    (net (code "98") (name "unconnected-(JX2-P$9-PadP$92)") (class "Default")
      (node (ref "JX2") (pin "P$92") (pinfunction "P$9_P$92") (pintype "bidirectional"))
    )
    (net (code "99") (name "unconnected-(JX2-P$12-PadP$89)") (class "Default")
      (node (ref "JX2") (pin "P$89") (pinfunction "P$12_P$89") (pintype "bidirectional"))
    )
    (net (code "100") (name "unconnected-(JX2-P$13-PadP$88)") (class "Default")
      (node (ref "JX2") (pin "P$88") (pinfunction "P$13_P$88") (pintype "bidirectional"))
    )
    (net (code "101") (name "unconnected-(JX2-P$14-PadP$87)") (class "Default")
      (node (ref "JX2") (pin "P$87") (pinfunction "P$14_P$87") (pintype "bidirectional"))
    )
    (net (code "102") (name "unconnected-(JX2-P$17-PadP$84)") (class "Default")
      (node (ref "JX2") (pin "P$84") (pinfunction "P$17_P$84") (pintype "bidirectional"))
    )
    (net (code "103") (name "unconnected-(JX2-P$19-PadP$82)") (class "Default")
      (node (ref "JX2") (pin "P$82") (pinfunction "P$19_P$82") (pintype "bidirectional"))
    )
    (net (code "104") (name "unconnected-(JX2-P$20-PadP$81)") (class "Default")
      (node (ref "JX2") (pin "P$81") (pinfunction "P$20_P$81") (pintype "bidirectional"))
    )
    (net (code "105") (name "unconnected-(JX2-P$23-PadP$78)") (class "Default")
      (node (ref "JX2") (pin "P$78") (pinfunction "P$23_P$78") (pintype "bidirectional"))
    )
    (net (code "106") (name "unconnected-(JX2-P$25-PadP$76)") (class "Default")
      (node (ref "JX2") (pin "P$76") (pinfunction "P$25_P$76") (pintype "bidirectional"))
    )
    (net (code "107") (name "unconnected-(JX2-P$29-PadP$72)") (class "Default")
      (node (ref "JX2") (pin "P$72") (pinfunction "P$29_P$72") (pintype "bidirectional"))
    )
    (net (code "108") (name "unconnected-(JX2-P$31-PadP$70)") (class "Default")
      (node (ref "JX2") (pin "P$70") (pinfunction "P$31_P$70") (pintype "bidirectional"))
    )
    (net (code "109") (name "unconnected-(JX2-P$35-PadP$66)") (class "Default")
      (node (ref "JX2") (pin "P$66") (pinfunction "P$35_P$66") (pintype "bidirectional"))
    )
    (net (code "110") (name "unconnected-(JX2-P$36-PadP$65)") (class "Default")
      (node (ref "JX2") (pin "P$65") (pinfunction "P$36_P$65") (pintype "bidirectional"))
    )
    (net (code "111") (name "unconnected-(JX2-P$37-PadP$64)") (class "Default")
      (node (ref "JX2") (pin "P$64") (pinfunction "P$37_P$64") (pintype "bidirectional"))
    )
    (net (code "112") (name "unconnected-(JX2-P$38-PadP$63)") (class "Default")
      (node (ref "JX2") (pin "P$63") (pinfunction "P$38_P$63") (pintype "bidirectional"))
    )
    (net (code "113") (name "unconnected-(JX2-P$41-PadP$60)") (class "Default")
      (node (ref "JX2") (pin "P$60") (pinfunction "P$41_P$60") (pintype "bidirectional"))
    )
    (net (code "114") (name "unconnected-(JX2-P$42-PadP$59)") (class "Default")
      (node (ref "JX2") (pin "P$59") (pinfunction "P$42_P$59") (pintype "bidirectional"))
    )
    (net (code "115") (name "unconnected-(JX2-P$43-PadP$58)") (class "Default")
      (node (ref "JX2") (pin "P$58") (pinfunction "P$43_P$58") (pintype "bidirectional"))
    )
    (net (code "116") (name "unconnected-(JX2-P$44-PadP$57)") (class "Default")
      (node (ref "JX2") (pin "P$57") (pinfunction "P$44_P$57") (pintype "bidirectional"))
    )
    (net (code "117") (name "unconnected-(JX2-P$47-PadP$54)") (class "Default")
      (node (ref "JX2") (pin "P$54") (pinfunction "P$47_P$54") (pintype "bidirectional"))
    )
    (net (code "118") (name "unconnected-(JX2-P$49-PadP$52)") (class "Default")
      (node (ref "JX2") (pin "P$52") (pinfunction "P$49_P$52") (pintype "bidirectional"))
    )
    (net (code "119") (name "unconnected-(JX2-P$50-PadP$51)") (class "Default")
      (node (ref "JX2") (pin "P$51") (pinfunction "P$50_P$51") (pintype "bidirectional"))
    )
    (net (code "120") (name "unconnected-(JX2-P$53-PadP$48)") (class "Default")
      (node (ref "JX2") (pin "P$48") (pinfunction "P$53_P$48") (pintype "bidirectional"))
    )
    (net (code "121") (name "unconnected-(JX2-P$54-PadP$47)") (class "Default")
      (node (ref "JX2") (pin "P$47") (pinfunction "P$54_P$47") (pintype "bidirectional"))
    )
    (net (code "122") (name "unconnected-(JX2-P$55-PadP$46)") (class "Default")
      (node (ref "JX2") (pin "P$46") (pinfunction "P$55_P$46") (pintype "bidirectional"))
    )
    (net (code "123") (name "unconnected-(JX2-P$56-PadP$45)") (class "Default")
      (node (ref "JX2") (pin "P$45") (pinfunction "P$56_P$45") (pintype "bidirectional"))
    )
    (net (code "124") (name "unconnected-(JX2-P$61-PadP$40)") (class "Default")
      (node (ref "JX2") (pin "P$40") (pinfunction "P$61_P$40") (pintype "bidirectional"))
    )
    (net (code "125") (name "unconnected-(JX2-P$62-PadP$39)") (class "Default")
      (node (ref "JX2") (pin "P$39") (pinfunction "P$62_P$39") (pintype "bidirectional"))
    )
    (net (code "126") (name "unconnected-(JX2-P$63-PadP$38)") (class "Default")
      (node (ref "JX2") (pin "P$38") (pinfunction "P$63_P$38") (pintype "bidirectional"))
    )
    (net (code "127") (name "unconnected-(JX2-P$64-PadP$37)") (class "Default")
      (node (ref "JX2") (pin "P$37") (pinfunction "P$64_P$37") (pintype "bidirectional"))
    )
    (net (code "128") (name "unconnected-(JX2-P$67-PadP$34)") (class "Default")
      (node (ref "JX2") (pin "P$34") (pinfunction "P$67_P$34") (pintype "bidirectional"))
    )
    (net (code "129") (name "unconnected-(JX2-P$68-PadP$33)") (class "Default")
      (node (ref "JX2") (pin "P$33") (pinfunction "P$68_P$33") (pintype "bidirectional"))
    )
    (net (code "130") (name "unconnected-(JX2-P$69-PadP$32)") (class "Default")
      (node (ref "JX2") (pin "P$32") (pinfunction "P$69_P$32") (pintype "bidirectional"))
    )
    (net (code "131") (name "unconnected-(JX2-P$70-PadP$31)") (class "Default")
      (node (ref "JX2") (pin "P$31") (pinfunction "P$70_P$31") (pintype "bidirectional"))
    )
    (net (code "132") (name "unconnected-(JX2-P$73-PadP$28)") (class "Default")
      (node (ref "JX2") (pin "P$28") (pinfunction "P$73_P$28") (pintype "bidirectional"))
    )
    (net (code "133") (name "unconnected-(JX2-P$74-PadP$27)") (class "Default")
      (node (ref "JX2") (pin "P$27") (pinfunction "P$74_P$27") (pintype "bidirectional"))
    )
    (net (code "134") (name "unconnected-(JX2-P$75-PadP$26)") (class "Default")
      (node (ref "JX2") (pin "P$26") (pinfunction "P$75_P$26") (pintype "bidirectional"))
    )
    (net (code "135") (name "unconnected-(JX2-P$76-PadP$25)") (class "Default")
      (node (ref "JX2") (pin "P$25") (pinfunction "P$76_P$25") (pintype "bidirectional"))
    )
    (net (code "136") (name "unconnected-(JX2-P$81-PadP$20)") (class "Default")
      (node (ref "JX2") (pin "P$20") (pinfunction "P$81_P$20") (pintype "bidirectional"))
    )
    (net (code "137") (name "unconnected-(JX2-P$82-PadP$19)") (class "Default")
      (node (ref "JX2") (pin "P$19") (pinfunction "P$82_P$19") (pintype "bidirectional"))
    )
    (net (code "138") (name "unconnected-(JX2-P$83-PadP$18)") (class "Default")
      (node (ref "JX2") (pin "P$18") (pinfunction "P$83_P$18") (pintype "bidirectional"))
    )
    (net (code "139") (name "unconnected-(JX2-P$84-PadP$17)") (class "Default")
      (node (ref "JX2") (pin "P$17") (pinfunction "P$84_P$17") (pintype "bidirectional"))
    )
    (net (code "140") (name "unconnected-(JX2-P$87-PadP$14)") (class "Default")
      (node (ref "JX2") (pin "P$14") (pinfunction "P$87_P$14") (pintype "bidirectional"))
    )
    (net (code "141") (name "unconnected-(JX2-P$88-PadP$13)") (class "Default")
      (node (ref "JX2") (pin "P$13") (pinfunction "P$88_P$13") (pintype "bidirectional"))
    )
    (net (code "142") (name "unconnected-(JX2-P$89-PadP$12)") (class "Default")
      (node (ref "JX2") (pin "P$12") (pinfunction "P$89_P$12") (pintype "bidirectional"))
    )
    (net (code "143") (name "unconnected-(JX2-P$90-PadP$11)") (class "Default")
      (node (ref "JX2") (pin "P$11") (pinfunction "P$90_P$11") (pintype "bidirectional"))
    )
    (net (code "144") (name "unconnected-(JX2-P$93-PadP$8)") (class "Default")
      (node (ref "JX2") (pin "P$8") (pinfunction "P$93_P$8") (pintype "bidirectional"))
    )
    (net (code "145") (name "unconnected-(JX2-P$94-PadP$7)") (class "Default")
      (node (ref "JX2") (pin "P$7") (pinfunction "P$94_P$7") (pintype "bidirectional"))
    )
    (net (code "146") (name "unconnected-(JX2-P$95-PadP$6)") (class "Default")
      (node (ref "JX2") (pin "P$6") (pinfunction "P$95_P$6") (pintype "bidirectional"))
    )
    (net (code "147") (name "unconnected-(JX2-P$96-PadP$5)") (class "Default")
      (node (ref "JX2") (pin "P$5") (pinfunction "P$96_P$5") (pintype "bidirectional"))
    )
    (net (code "148") (name "unconnected-(JX2-P$97-PadP$4)") (class "Default")
      (node (ref "JX2") (pin "P$4") (pinfunction "P$97_P$4") (pintype "bidirectional"))
    )
    (net (code "149") (name "unconnected-(JX2-P$98-PadP$3)") (class "Default")
      (node (ref "JX2") (pin "P$3") (pinfunction "P$98_P$3") (pintype "bidirectional"))
    )
    (net (code "150") (name "unconnected-(JX2-P$99-PadP$2)") (class "Default")
      (node (ref "JX2") (pin "P$2") (pinfunction "P$99_P$2") (pintype "bidirectional"))
    )
    (net (code "151") (name "unconnected-(JX2-P$100-PadP$1)") (class "Default")
      (node (ref "JX2") (pin "P$1") (pinfunction "P$100_P$1") (pintype "bidirectional"))
    )
    (net (code "152") (name "unconnected-(U$2-~{CLK}-PadP$5)") (class "Default")
      (node (ref "U$2") (pin "P$5") (pinfunction "~{CLK}_P$5") (pintype "bidirectional"))
    )
  )
)
